# BSE_SCH.net
KiCad netlist of a schematic drawn in Altium Designer
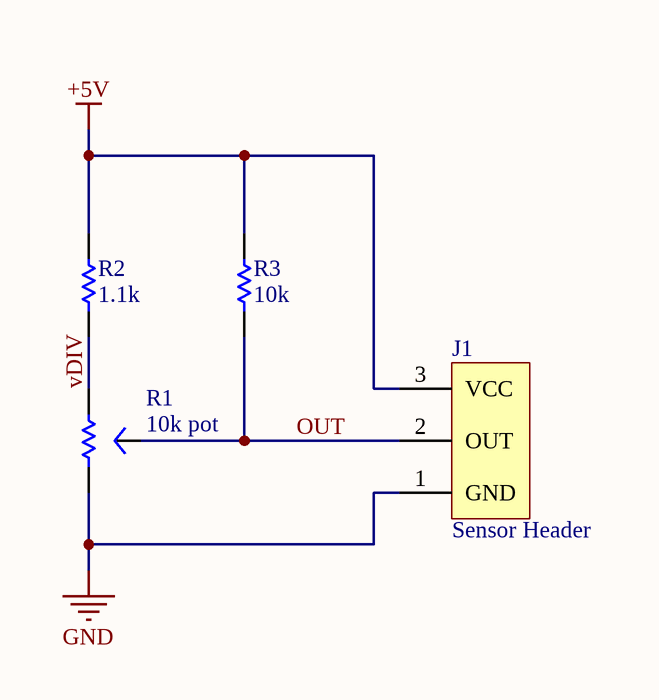
[diagram p0: BSE_SCH.SchDoc]

(export (version "E")
  (design (tool "Eeschema 10.0.6"))
  (components
    (comp (ref "J1")
      (value "Sensor Header")
      (footprint "Header3POS-SMD")
      (description "Conn Shrouded Header (4 Sides) HDR 3 POS 1.5mm Solder RA SMD Pico-SPOX™ T/R")
      (fields (field (name "MANUFACTURER") "Molex") (field (name "MANUFACTURER PART NUMBER") "0874380343"))
      (libsource (lib "BSE_SCH_lib") (part "Header3POS-SMD"))
    )
    (comp (ref "R1")
      (value "10k pot")
      (footprint "10k Rotary Encoder")
      (description "Res Cermet Trimmer 10K Ohm 30% 1(Elec)/1(Mech)Turn 4mm (11 X 14.9 X 3.1mm) Gull Wing SMD T/R")
      (fields
        (field (name "MANUFACTURER") "Murata")
        (field (name "MANUFACTURER PART NUMBER") "SV01A103AEA01R00")
      )
      (libsource (lib "BSE_SCH_lib") (part "10k rotary encoder"))
    )
    (comp (ref "R2")
      (value "1.1k")
      (footprint "RES 0603")
      (description "ERJPA3 Resistors 0.25W 0603 1K1 1%")
      (fields
        (field (name "MANUFACTURER") "Panasonic")
        (field (name "MANUFACTURER PART NUMBER") "ERJ-PA3F1101V")
      )
      (libsource (lib "BSE_SCH_lib") (part "RES 1.1k"))
    )
    (comp (ref "R3")
      (value "10k")
      (footprint "RES 0603")
      (description "RES SMD 10K OHM 1% 1/4W 0603")
      (fields (field (name "MANUFACTURER") "Rohm") (field (name "MANUFACTURER PART NUMBER") "ESR03EZPF1002"))
      (libsource (lib "BSE_SCH_lib") (part "RES 10k"))
    )
  )
  (nets
    (net (code "1") (name "+5V") (class "Default")
      (node (ref "J1") (pin "3") (pinfunction "VCC_3") (pintype "passive"))
      (node (ref "R2") (pin "2") (pinfunction "2_2") (pintype "passive"))
      (node (ref "R3") (pin "2") (pinfunction "2_2") (pintype "passive"))
    )
    (net (code "2") (name "/OUT") (class "Default")
      (node (ref "J1") (pin "2") (pinfunction "OUT_2") (pintype "passive"))
      (node (ref "R1") (pin "2") (pinfunction "2_2") (pintype "passive"))
      (node (ref "R3") (pin "1") (pinfunction "1_1") (pintype "passive"))
    )
    (net (code "3") (name "/vDIV") (class "Default")
      (node (ref "R1") (pin "3") (pinfunction "3_3") (pintype "passive"))
      (node (ref "R2") (pin "1") (pinfunction "1_1") (pintype "passive"))
    )
    (net (code "4") (name "GND") (class "Default")
      (node (ref "J1") (pin "1") (pinfunction "GND_1") (pintype "passive"))
      (node (ref "R1") (pin "1") (pinfunction "1_1") (pintype "passive"))
    )
  )
)
